# UCirKitUserStudy3.net
KiCad netlist of a schematic drawn in EAGLE
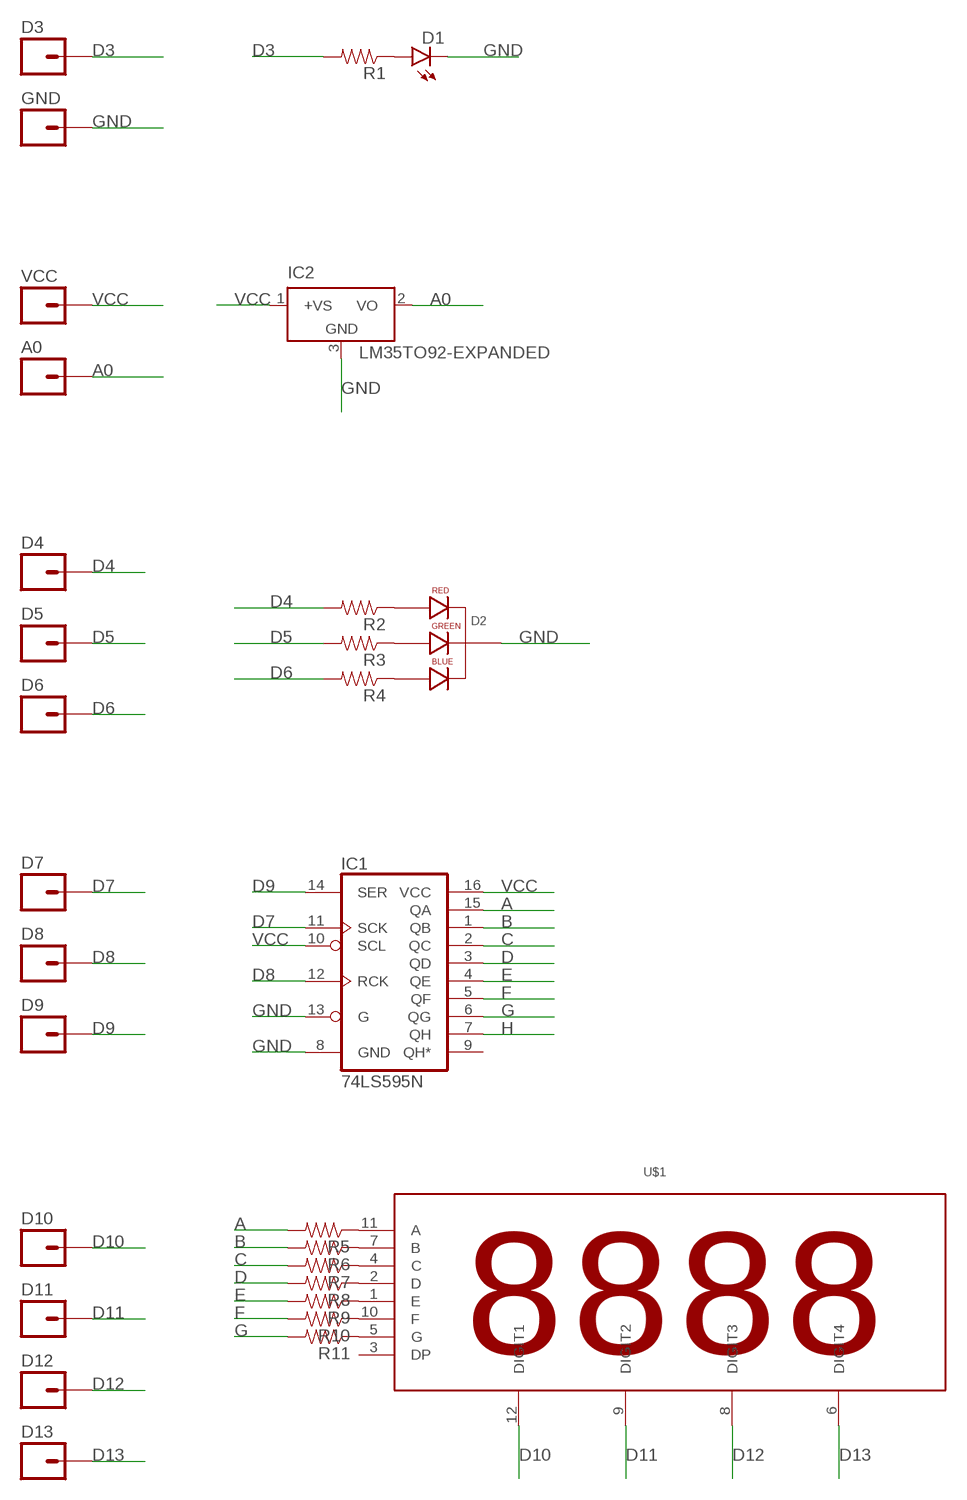
[diagram p0: schematic, sheet 1]

(export (version "E")
  (design (tool "Eeschema 10.0.6"))
  (components
    (comp (ref "A0")
      (value "M01PTH")
      (footprint "eagle-import:1X01")
      (libsource (lib "eagle-import") (part "M01PTH"))
    )
    (comp (ref "D1")
      (value "LEDLED3MM-EXPANDED")
      (footprint "eagle-import:LED3MM-EXPANDED")
      (libsource (lib "eagle-import") (part "LEDLED3MM-EXPANDED"))
    )
    (comp (ref "D2")
      (value "LED-RGB-CC-THRUEXPANDED")
      (footprint "eagle-import:LED-RGB-THRU-EXPANDED")
      (libsource (lib "eagle-import") (part "LED-RGB-CC-THRUEXPANDED"))
    )
    (comp (ref "D3")
      (value "M01PTH")
      (footprint "eagle-import:1X01")
      (libsource (lib "eagle-import") (part "M01PTH"))
    )
    (comp (ref "D4")
      (value "M01PTH")
      (footprint "eagle-import:1X01")
      (libsource (lib "eagle-import") (part "M01PTH"))
    )
    (comp (ref "D5")
      (value "M01PTH")
      (footprint "eagle-import:1X01")
      (libsource (lib "eagle-import") (part "M01PTH"))
    )
    (comp (ref "D6")
      (value "M01PTH")
      (footprint "eagle-import:1X01")
      (libsource (lib "eagle-import") (part "M01PTH"))
    )
    (comp (ref "D7")
      (value "M01PTH")
      (footprint "eagle-import:1X01")
      (libsource (lib "eagle-import") (part "M01PTH"))
    )
    (comp (ref "D8")
      (value "M01PTH")
      (footprint "eagle-import:1X01")
      (libsource (lib "eagle-import") (part "M01PTH"))
    )
    (comp (ref "D9")
      (value "M01PTH")
      (footprint "eagle-import:1X01")
      (libsource (lib "eagle-import") (part "M01PTH"))
    )
    (comp (ref "D10")
      (value "M01PTH")
      (footprint "eagle-import:1X01")
      (libsource (lib "eagle-import") (part "M01PTH"))
    )
    (comp (ref "D11")
      (value "M01PTH")
      (footprint "eagle-import:1X01")
      (libsource (lib "eagle-import") (part "M01PTH"))
    )
    (comp (ref "D12")
      (value "M01PTH")
      (footprint "eagle-import:1X01")
      (libsource (lib "eagle-import") (part "M01PTH"))
    )
    (comp (ref "D13")
      (value "M01PTH")
      (footprint "eagle-import:1X01")
      (libsource (lib "eagle-import") (part "M01PTH"))
    )
    (comp (ref "GND")
      (value "M01PTH")
      (footprint "eagle-import:1X01")
      (libsource (lib "eagle-import") (part "M01PTH"))
    )
    (comp (ref "IC1")
      (value "74LS595N")
      (footprint "eagle-import:DIL16")
      (libsource (lib "eagle-import") (part "74595NLS"))
    )
    (comp (ref "IC2")
      (value "LM35TO92-EXPANDED")
      (footprint "eagle-import:TO92-EXPANDED")
      (libsource (lib "eagle-import") (part "LM35TO92-EXPANDED"))
    )
    (comp (ref "R1")
      (value "1KOHM-1/4W-1%(PTH)PTH-EXPANDED")
      (footprint "eagle-import:PTH-EXPANDED")
      (libsource (lib "eagle-import") (part "1KOHM-1/4W-1%(PTH)PTH-EXPANDED"))
    )
    (comp (ref "R2")
      (value "1KOHM-1/4W-1%(PTH)PTH-EXPANDED")
      (footprint "eagle-import:PTH-EXPANDED")
      (libsource (lib "eagle-import") (part "1KOHM-1/4W-1%(PTH)PTH-EXPANDED"))
    )
    (comp (ref "R3")
      (value "1KOHM-1/4W-1%(PTH)PTH-EXPANDED")
      (footprint "eagle-import:PTH-EXPANDED")
      (libsource (lib "eagle-import") (part "1KOHM-1/4W-1%(PTH)PTH-EXPANDED"))
    )
    (comp (ref "R4")
      (value "1KOHM-1/4W-1%(PTH)PTH-EXPANDED")
      (footprint "eagle-import:PTH-EXPANDED")
      (libsource (lib "eagle-import") (part "1KOHM-1/4W-1%(PTH)PTH-EXPANDED"))
    )
    (comp (ref "R5")
      (value "1KOHM-1/4W-1%(PTH)PTH-EXPANDED")
      (footprint "eagle-import:PTH-EXPANDED")
      (libsource (lib "eagle-import") (part "1KOHM-1/4W-1%(PTH)PTH-EXPANDED"))
    )
    (comp (ref "R6")
      (value "1KOHM-1/4W-1%(PTH)PTH-EXPANDED")
      (footprint "eagle-import:PTH-EXPANDED")
      (libsource (lib "eagle-import") (part "1KOHM-1/4W-1%(PTH)PTH-EXPANDED"))
    )
    (comp (ref "R7")
      (value "1KOHM-1/4W-1%(PTH)PTH-EXPANDED")
      (footprint "eagle-import:PTH-EXPANDED")
      (libsource (lib "eagle-import") (part "1KOHM-1/4W-1%(PTH)PTH-EXPANDED"))
    )
    (comp (ref "R8")
      (value "1KOHM-1/4W-1%(PTH)PTH-EXPANDED")
      (footprint "eagle-import:PTH-EXPANDED")
      (libsource (lib "eagle-import") (part "1KOHM-1/4W-1%(PTH)PTH-EXPANDED"))
    )
    (comp (ref "R9")
      (value "1KOHM-1/4W-1%(PTH)PTH-EXPANDED")
      (footprint "eagle-import:PTH-EXPANDED")
      (libsource (lib "eagle-import") (part "1KOHM-1/4W-1%(PTH)PTH-EXPANDED"))
    )
    (comp (ref "R10")
      (value "1KOHM-1/4W-1%(PTH)PTH-EXPANDED")
      (footprint "eagle-import:PTH-EXPANDED")
      (libsource (lib "eagle-import") (part "1KOHM-1/4W-1%(PTH)PTH-EXPANDED"))
    )
    (comp (ref "R11")
      (value "1KOHM-1/4W-1%(PTH)PTH-EXPANDED")
      (footprint "eagle-import:PTH-EXPANDED")
      (libsource (lib "eagle-import") (part "1KOHM-1/4W-1%(PTH)PTH-EXPANDED"))
    )
    (comp (ref "U$1")
      (value "4DIGIT_SEVEN_SEGMENT4DIGIT_SEVEN_SEGMENT")
      (footprint "eagle-import:4DIGIT_SEVEN_SEGMENT")
      (libsource (lib "eagle-import") (part "4DIGIT_SEVEN_SEGMENT4DIGIT_SEVEN_SEGMENT"))
    )
    (comp (ref "VCC")
      (value "M01PTH")
      (footprint "eagle-import:1X01")
      (libsource (lib "eagle-import") (part "M01PTH"))
    )
  )
  (nets
    (net (code "1") (name "/A") (class "Default")
      (node (ref "IC1") (pin "15") (pinfunction "QA_15") (pintype "tri_state"))
      (node (ref "R5") (pin "P$2") (pinfunction "2_P$2") (pintype "passive"))
    )
    (net (code "2") (name "/A0") (class "Default")
      (node (ref "A0") (pin "1") (pinfunction "1_1") (pintype "passive"))
      (node (ref "IC2") (pin "2") (pinfunction "VO_2") (pintype "input"))
    )
    (net (code "3") (name "/B") (class "Default")
      (node (ref "IC1") (pin "1") (pinfunction "QB_1") (pintype "tri_state"))
      (node (ref "R6") (pin "P$2") (pinfunction "2_P$2") (pintype "passive"))
    )
    (net (code "4") (name "/C") (class "Default")
      (node (ref "IC1") (pin "2") (pinfunction "QC_2") (pintype "tri_state"))
      (node (ref "R7") (pin "P$2") (pinfunction "2_P$2") (pintype "passive"))
    )
    (net (code "5") (name "/D") (class "Default")
      (node (ref "IC1") (pin "3") (pinfunction "QD_3") (pintype "tri_state"))
      (node (ref "R8") (pin "P$2") (pinfunction "2_P$2") (pintype "passive"))
    )
    (net (code "6") (name "/D3") (class "Default")
      (node (ref "D3") (pin "1") (pinfunction "1_1") (pintype "passive"))
      (node (ref "R1") (pin "P$2") (pinfunction "2_P$2") (pintype "passive"))
    )
    (net (code "7") (name "/D4") (class "Default")
      (node (ref "D4") (pin "1") (pinfunction "1_1") (pintype "passive"))
      (node (ref "R2") (pin "P$2") (pinfunction "2_P$2") (pintype "passive"))
    )
    (net (code "8") (name "/D5") (class "Default")
      (node (ref "D5") (pin "1") (pinfunction "1_1") (pintype "passive"))
      (node (ref "R3") (pin "P$2") (pinfunction "2_P$2") (pintype "passive"))
    )
    (net (code "9") (name "/D6") (class "Default")
      (node (ref "D6") (pin "1") (pinfunction "1_1") (pintype "passive"))
      (node (ref "R4") (pin "P$2") (pinfunction "2_P$2") (pintype "passive"))
    )
    (net (code "10") (name "/D7") (class "Default")
      (node (ref "D7") (pin "1") (pinfunction "1_1") (pintype "passive"))
      (node (ref "IC1") (pin "11") (pinfunction "SCK_11") (pintype "input"))
    )
    (net (code "11") (name "/D8") (class "Default")
      (node (ref "D8") (pin "1") (pinfunction "1_1") (pintype "passive"))
      (node (ref "IC1") (pin "12") (pinfunction "RCK_12") (pintype "input"))
    )
    (net (code "12") (name "/D9") (class "Default")
      (node (ref "D9") (pin "1") (pinfunction "1_1") (pintype "passive"))
      (node (ref "IC1") (pin "14") (pinfunction "SER_14") (pintype "input"))
    )
    (net (code "13") (name "/D10") (class "Default")
      (node (ref "D10") (pin "1") (pinfunction "1_1") (pintype "passive"))
      (node (ref "U$1") (pin "12") (pinfunction "DIGIT1_12") (pintype "bidirectional"))
    )
    (net (code "14") (name "/D11") (class "Default")
      (node (ref "D11") (pin "1") (pinfunction "1_1") (pintype "passive"))
      (node (ref "U$1") (pin "9") (pinfunction "DIGIT2_9") (pintype "bidirectional"))
    )
    (net (code "15") (name "/D12") (class "Default")
      (node (ref "D12") (pin "1") (pinfunction "1_1") (pintype "passive"))
      (node (ref "U$1") (pin "8") (pinfunction "DIGIT3_8") (pintype "bidirectional"))
    )
    (net (code "16") (name "/D13") (class "Default")
      (node (ref "D13") (pin "1") (pinfunction "1_1") (pintype "passive"))
      (node (ref "U$1") (pin "6") (pinfunction "DIGIT4_6") (pintype "bidirectional"))
    )
    (net (code "17") (name "/E") (class "Default")
      (node (ref "IC1") (pin "4") (pinfunction "QE_4") (pintype "tri_state"))
      (node (ref "R9") (pin "P$2") (pinfunction "2_P$2") (pintype "passive"))
    )
    (net (code "18") (name "/F") (class "Default")
      (node (ref "IC1") (pin "5") (pinfunction "QF_5") (pintype "tri_state"))
      (node (ref "R10") (pin "P$2") (pinfunction "2_P$2") (pintype "passive"))
    )
    (net (code "19") (name "/G") (class "Default")
      (node (ref "IC1") (pin "6") (pinfunction "QG_6") (pintype "tri_state"))
      (node (ref "R11") (pin "P$2") (pinfunction "2_P$2") (pintype "passive"))
    )
    (net (code "20") (name "/GND") (class "Default")
      (node (ref "D1") (pin "K") (pinfunction "C_K") (pintype "passive"))
      (node (ref "D2") (pin "2") (pinfunction "CATHODE_2") (pintype "bidirectional"))
      (node (ref "GND") (pin "1") (pinfunction "1_1") (pintype "passive"))
      (node (ref "IC1") (pin "13") (pinfunction "G_13") (pintype "input"))
      (node (ref "IC1") (pin "8") (pinfunction "GND_8") (pintype "power_in"))
      (node (ref "IC2") (pin "3") (pinfunction "GND_3") (pintype "power_in"))
    )
    (net (code "21") (name "/H") (class "Default")
      (node (ref "IC1") (pin "7") (pinfunction "QH_7") (pintype "tri_state"))
    )
    (net (code "22") (name "/VCC") (class "Default")
      (node (ref "IC1") (pin "10") (pinfunction "SCL_10") (pintype "input"))
      (node (ref "IC1") (pin "16") (pinfunction "VCC_16") (pintype "power_in"))
      (node (ref "IC2") (pin "1") (pinfunction "+VS_1") (pintype "input"))
      (node (ref "VCC") (pin "1") (pinfunction "1_1") (pintype "passive"))
    )
    (net (code "23") (name "Net-(D2-BLUE_CATHODE)") (class "Default")
      (node (ref "D2") (pin "4") (pinfunction "BLUE_CATHODE_4") (pintype "bidirectional"))
      (node (ref "R4") (pin "P$1") (pinfunction "1_P$1") (pintype "passive"))
    )
    (net (code "24") (name "Net-(D2-GREEN_CATHODE)") (class "Default")
      (node (ref "D2") (pin "3") (pinfunction "GREEN_CATHODE_3") (pintype "bidirectional"))
      (node (ref "R3") (pin "P$1") (pinfunction "1_P$1") (pintype "passive"))
    )
    (net (code "25") (name "Net-(D2-RED_CATHODE)") (class "Default")
      (node (ref "D2") (pin "1") (pinfunction "RED_CATHODE_1") (pintype "bidirectional"))
      (node (ref "R2") (pin "P$1") (pinfunction "1_P$1") (pintype "passive"))
    )
    (net (code "26") (name "Net-(R1-1)") (class "Default")
      (node (ref "D1") (pin "A") (pinfunction "A_A") (pintype "passive"))
      (node (ref "R1") (pin "P$1") (pinfunction "1_P$1") (pintype "passive"))
    )
    (net (code "27") (name "Net-(R5-1)") (class "Default")
      (node (ref "R5") (pin "P$1") (pinfunction "1_P$1") (pintype "passive"))
      (node (ref "U$1") (pin "11") (pinfunction "A_11") (pintype "bidirectional"))
    )
    (net (code "28") (name "Net-(R6-1)") (class "Default")
      (node (ref "R6") (pin "P$1") (pinfunction "1_P$1") (pintype "passive"))
      (node (ref "U$1") (pin "7") (pinfunction "B_7") (pintype "bidirectional"))
    )
    (net (code "29") (name "Net-(R7-1)") (class "Default")
      (node (ref "R7") (pin "P$1") (pinfunction "1_P$1") (pintype "passive"))
      (node (ref "U$1") (pin "4") (pinfunction "C_4") (pintype "bidirectional"))
    )
    (net (code "30") (name "Net-(R8-1)") (class "Default")
      (node (ref "R8") (pin "P$1") (pinfunction "1_P$1") (pintype "passive"))
      (node (ref "U$1") (pin "2") (pinfunction "D_2") (pintype "bidirectional"))
    )
    (net (code "31") (name "Net-(R9-1)") (class "Default")
      (node (ref "R9") (pin "P$1") (pinfunction "1_P$1") (pintype "passive"))
      (node (ref "U$1") (pin "1") (pinfunction "E_1") (pintype "bidirectional"))
    )
    (net (code "32") (name "Net-(R10-1)") (class "Default")
      (node (ref "R10") (pin "P$1") (pinfunction "1_P$1") (pintype "passive"))
      (node (ref "U$1") (pin "10") (pinfunction "F_10") (pintype "bidirectional"))
    )
    (net (code "33") (name "Net-(R11-1)") (class "Default")
      (node (ref "R11") (pin "P$1") (pinfunction "1_P$1") (pintype "passive"))
      (node (ref "U$1") (pin "5") (pinfunction "G_5") (pintype "bidirectional"))
    )
    (net (code "34") (name "unconnected-(IC1-QH*-Pad9)") (class "Default")
      (node (ref "IC1") (pin "9") (pinfunction "QH*_9") (pintype "tri_state"))
    )
    (net (code "35") (name "unconnected-(U$1-DP-Pad3)") (class "Default")
      (node (ref "U$1") (pin "3") (pinfunction "DP_3") (pintype "bidirectional"))
    )
  )
)
